# Stepper_Motor_Driver_2.net
KiCad netlist of a schematic drawn in Altium Designer
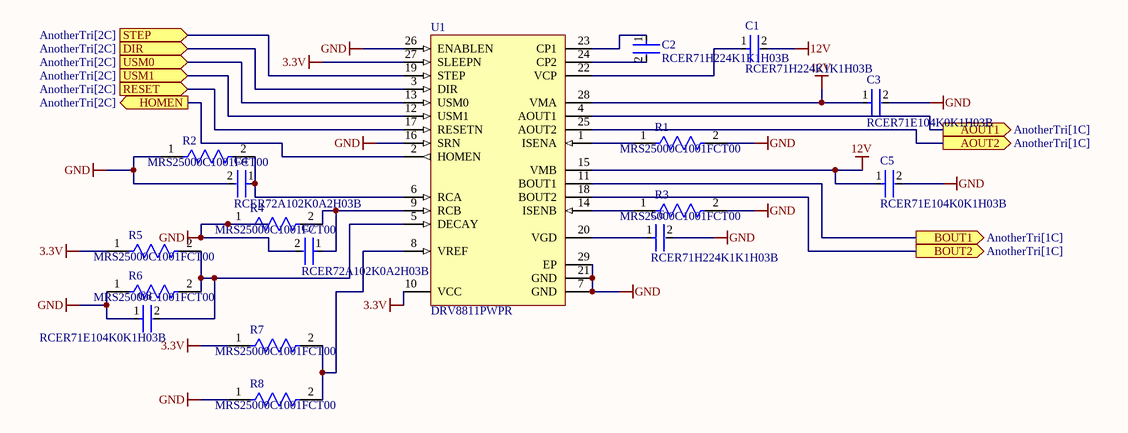
[diagram p0: Stepper Motor Driver 2.SchDoc]

(export (version "E")
  (design (tool "Eeschema 10.0.6"))
  (components
    (comp (ref "C1")
      (value "RCER71H224K1K1H03B")
      (footprint "FP-RCE1K1-2_5-MFG")
      (description "Cap Ceramic Monolithic 220nF 50V 10% Thru-Hole Bulk")
      (fields (field (name "TOLERANCE") "10%"))
      (libsource (lib "Altium Content Vault") (part "02cd4be3c70576c341d710602a673aa"))
    )
    (comp (ref "C2")
      (value "RCER71H224K1K1H03B")
      (footprint "FP-RCE1K1-2_5-MFG")
      (description "Cap Ceramic Monolithic 220nF 50V 10% Thru-Hole Bulk")
      (fields (field (name "TOLERANCE") "10%"))
      (libsource (lib "Altium Content Vault") (part "02cd4be3c70576c341d710602a673aa"))
    )
    (comp (ref "C3")
      (value "RCER71E104K0K1H03B")
      (footprint "FP-RCE0K1-MFG")
      (description "Cap Ceramic 100nF 25V X7R ±10% Radial 5mm +125°C Automotive Bulk")
      (libsource (lib "Altium Content Vault") (part "b4654b650e69147ec39a6b967a45e02"))
    )
    (comp (ref "C4")
      (value "RCER72A102K0A2H03B")
      (footprint "FP-RCE0DB-MFG")
      (description "Cap Ceramic 1nF 100V X7R ±10% Radial 2.5mm +125°C Bulk")
      (fields (field (name "TOLERANCE") "10%"))
      (libsource (lib "Altium Content Vault") (part "b4654b650e69147ec39a6b967a45e02"))
    )
    (comp (ref "C5")
      (value "RCER71E104K0K1H03B")
      (footprint "FP-RCE0K1-MFG")
      (description "Cap Ceramic 100nF 25V X7R ±10% Radial 5mm +125°C Automotive Bulk")
      (libsource (lib "Altium Content Vault") (part "b4654b650e69147ec39a6b967a45e02"))
    )
    (comp (ref "C6")
      (value "RCER71H224K1K1H03B")
      (footprint "FP-RCE1K1-2_5-MFG")
      (description "Cap Ceramic Monolithic 220nF 50V 10% Thru-Hole Bulk")
      (fields (field (name "TOLERANCE") "10%"))
      (libsource (lib "Altium Content Vault") (part "02cd4be3c70576c341d710602a673aa"))
    )
    (comp (ref "C7")
      (value "RCER72A102K0A2H03B")
      (footprint "FP-RCE0DB-MFG")
      (description "Cap Ceramic 1nF 100V X7R ±10% Radial 2.5mm +125°C Bulk")
      (fields (field (name "TOLERANCE") "10%"))
      (libsource (lib "Altium Content Vault") (part "b4654b650e69147ec39a6b967a45e02"))
    )
    (comp (ref "C8")
      (value "RCER71E104K0K1H03B")
      (footprint "FP-RCE0K1-MFG")
      (description "Cap Ceramic 100nF 25V X7R ±10% Radial 5mm +125°C Automotive Bulk")
      (libsource (lib "Altium Content Vault") (part "b4654b650e69147ec39a6b967a45e02"))
    )
    (comp (ref "R1")
      (value "MRS25000C1001FCT00")
      (footprint "FP-MRS25-MFG")
      (description "RES 1K OHM 0.6W 1% AXIAL")
      (fields (field (name "TOLERANCE") "1%"))
      (libsource (lib "Altium Content Vault") (part "1029c3af85768c4190bb7ad29bc67b5"))
    )
    (comp (ref "R2")
      (value "MRS25000C1001FCT00")
      (footprint "FP-MRS25-MFG")
      (description "RES 1K OHM 0.6W 1% AXIAL")
      (fields (field (name "TOLERANCE") "1%"))
      (libsource (lib "Altium Content Vault") (part "1029c3af85768c4190bb7ad29bc67b5"))
    )
    (comp (ref "R3")
      (value "MRS25000C1001FCT00")
      (footprint "FP-MRS25-MFG")
      (description "RES 1K OHM 0.6W 1% AXIAL")
      (fields (field (name "TOLERANCE") "1%"))
      (libsource (lib "Altium Content Vault") (part "1029c3af85768c4190bb7ad29bc67b5"))
    )
    (comp (ref "R4")
      (value "MRS25000C1001FCT00")
      (footprint "FP-MRS25-MFG")
      (description "RES 1K OHM 0.6W 1% AXIAL")
      (fields (field (name "TOLERANCE") "1%"))
      (libsource (lib "Altium Content Vault") (part "1029c3af85768c4190bb7ad29bc67b5"))
    )
    (comp (ref "R5")
      (value "MRS25000C1001FCT00")
      (footprint "FP-MRS25-MFG")
      (description "RES 1K OHM 0.6W 1% AXIAL")
      (fields (field (name "TOLERANCE") "1%"))
      (libsource (lib "Altium Content Vault") (part "1029c3af85768c4190bb7ad29bc67b5"))
    )
    (comp (ref "R6")
      (value "MRS25000C1001FCT00")
      (footprint "FP-MRS25-MFG")
      (description "RES 1K OHM 0.6W 1% AXIAL")
      (fields (field (name "TOLERANCE") "1%"))
      (libsource (lib "Altium Content Vault") (part "1029c3af85768c4190bb7ad29bc67b5"))
    )
    (comp (ref "R7")
      (value "MRS25000C1001FCT00")
      (footprint "FP-MRS25-MFG")
      (description "RES 1K OHM 0.6W 1% AXIAL")
      (fields (field (name "TOLERANCE") "1%"))
      (libsource (lib "Altium Content Vault") (part "1029c3af85768c4190bb7ad29bc67b5"))
    )
    (comp (ref "R8")
      (value "MRS25000C1001FCT00")
      (footprint "FP-MRS25-MFG")
      (description "RES 1K OHM 0.6W 1% AXIAL")
      (fields (field (name "TOLERANCE") "1%"))
      (libsource (lib "Altium Content Vault") (part "1029c3af85768c4190bb7ad29bc67b5"))
    )
    (comp (ref "U1")
      (value "DRV8811PWPR")
      (footprint "PWP0028C_L")
      (libsource (lib "Altium Content Vault") (part "TI-DRV8811PWP28-5230X2750TP"))
    )
  )
  (nets
    (net (code "1") (name "/AOUT1") (class "Default")
      (node (ref "U1") (pin "4") (pinfunction "AOUT1_4") (pintype "power_in"))
    )
    (net (code "2") (name "/AOUT2") (class "Default")
      (node (ref "U1") (pin "25") (pinfunction "AOUT2_25") (pintype "power_in"))
    )
    (net (code "3") (name "/BOUT1") (class "Default")
      (node (ref "U1") (pin "11") (pinfunction "BOUT1_11") (pintype "power_in"))
    )
    (net (code "4") (name "/BOUT2") (class "Default")
      (node (ref "U1") (pin "18") (pinfunction "BOUT2_18") (pintype "power_in"))
    )
    (net (code "5") (name "/DIR") (class "Default")
      (node (ref "U1") (pin "3") (pinfunction "DIR_3") (pintype "input"))
    )
    (net (code "6") (name "/HOMEN") (class "Default")
      (node (ref "U1") (pin "2") (pinfunction "HOMEN_2") (pintype "output"))
    )
    (net (code "7") (name "/RESET") (class "Default")
      (node (ref "U1") (pin "17") (pinfunction "RESETN_17") (pintype "input"))
    )
    (net (code "8") (name "/STEP") (class "Default")
      (node (ref "U1") (pin "19") (pinfunction "STEP_19") (pintype "input"))
    )
    (net (code "9") (name "/USM0") (class "Default")
      (node (ref "U1") (pin "13") (pinfunction "USM0_13") (pintype "input"))
    )
    (net (code "10") (name "/USM1") (class "Default")
      (node (ref "U1") (pin "12") (pinfunction "USM1_12") (pintype "input"))
    )
    (net (code "11") (name "3.3V") (class "Default")
      (node (ref "R5") (pin "1") (pinfunction "1_1") (pintype "passive"))
      (node (ref "R7") (pin "1") (pinfunction "1_1") (pintype "passive"))
      (node (ref "U1") (pin "10") (pinfunction "VCC_10") (pintype "power_in"))
      (node (ref "U1") (pin "27") (pinfunction "SLEEPN_27") (pintype "input"))
    )
    (net (code "12") (name "12V") (class "Default")
      (node (ref "C1") (pin "2") (pinfunction "2_2") (pintype "passive"))
      (node (ref "C3") (pin "1") (pinfunction "1_1") (pintype "passive"))
      (node (ref "C5") (pin "1") (pinfunction "1_1") (pintype "passive"))
      (node (ref "U1") (pin "15") (pinfunction "VMB_15") (pintype "power_in"))
      (node (ref "U1") (pin "28") (pinfunction "VMA_28") (pintype "power_in"))
    )
    (net (code "13") (name "GND") (class "Default")
      (node (ref "C3") (pin "2") (pinfunction "2_2") (pintype "passive"))
      (node (ref "C4") (pin "2") (pinfunction "2_2") (pintype "passive"))
      (node (ref "C5") (pin "2") (pinfunction "2_2") (pintype "passive"))
      (node (ref "C6") (pin "2") (pinfunction "2_2") (pintype "passive"))
      (node (ref "C7") (pin "2") (pinfunction "2_2") (pintype "passive"))
      (node (ref "C8") (pin "1") (pinfunction "1_1") (pintype "passive"))
      (node (ref "R1") (pin "2") (pinfunction "2_2") (pintype "passive"))
      (node (ref "R2") (pin "1") (pinfunction "1_1") (pintype "passive"))
      (node (ref "R3") (pin "2") (pinfunction "2_2") (pintype "passive"))
      (node (ref "R4") (pin "1") (pinfunction "1_1") (pintype "passive"))
      (node (ref "R6") (pin "1") (pinfunction "1_1") (pintype "passive"))
      (node (ref "R8") (pin "1") (pinfunction "1_1") (pintype "passive"))
      (node (ref "U1") (pin "16") (pinfunction "SRN_16") (pintype "input"))
      (node (ref "U1") (pin "21") (pinfunction "GND_21") (pintype "power_in"))
      (node (ref "U1") (pin "26") (pinfunction "ENABLEN_26") (pintype "input"))
      (node (ref "U1") (pin "29") (pinfunction "EP_29") (pintype "power_in"))
      (node (ref "U1") (pin "7") (pinfunction "GND_7") (pintype "power_in"))
    )
    (net (code "14") (name "Net-(U1-CP1)") (class "Default")
      (node (ref "C2") (pin "1") (pinfunction "1_1") (pintype "passive"))
      (node (ref "U1") (pin "23") (pinfunction "CP1_23") (pintype "passive"))
    )
    (net (code "15") (name "Net-(U1-CP2)") (class "Default")
      (node (ref "C2") (pin "2") (pinfunction "2_2") (pintype "passive"))
      (node (ref "U1") (pin "24") (pinfunction "CP2_24") (pintype "passive"))
    )
    (net (code "16") (name "Net-(U1-DECAY)") (class "Default")
      (node (ref "C8") (pin "2") (pinfunction "2_2") (pintype "passive"))
      (node (ref "R5") (pin "2") (pinfunction "2_2") (pintype "passive"))
      (node (ref "R6") (pin "2") (pinfunction "2_2") (pintype "passive"))
      (node (ref "U1") (pin "5") (pinfunction "DECAY_5") (pintype "input"))
    )
    (net (code "17") (name "Net-(U1-ISENA)") (class "Default")
      (node (ref "R1") (pin "1") (pinfunction "1_1") (pintype "passive"))
      (node (ref "U1") (pin "1") (pinfunction "ISENA_1") (pintype "input"))
    )
    (net (code "18") (name "Net-(U1-ISENB)") (class "Default")
      (node (ref "R3") (pin "1") (pinfunction "1_1") (pintype "passive"))
      (node (ref "U1") (pin "14") (pinfunction "ISENB_14") (pintype "input"))
    )
    (net (code "19") (name "Net-(U1-RCA)") (class "Default")
      (node (ref "C4") (pin "1") (pinfunction "1_1") (pintype "passive"))
      (node (ref "R2") (pin "2") (pinfunction "2_2") (pintype "passive"))
      (node (ref "U1") (pin "6") (pinfunction "RCA_6") (pintype "input"))
    )
    (net (code "20") (name "Net-(U1-RCB)") (class "Default")
      (node (ref "C7") (pin "1") (pinfunction "1_1") (pintype "passive"))
      (node (ref "R4") (pin "2") (pinfunction "2_2") (pintype "passive"))
      (node (ref "U1") (pin "9") (pinfunction "RCB_9") (pintype "input"))
    )
    (net (code "21") (name "Net-(U1-VCP)") (class "Default")
      (node (ref "C1") (pin "1") (pinfunction "1_1") (pintype "passive"))
      (node (ref "U1") (pin "22") (pinfunction "VCP_22") (pintype "power_in"))
    )
    (net (code "22") (name "Net-(U1-VGD)") (class "Default")
      (node (ref "C6") (pin "1") (pinfunction "1_1") (pintype "passive"))
      (node (ref "U1") (pin "20") (pinfunction "VGD_20") (pintype "power_in"))
    )
    (net (code "23") (name "Net-(U1-VREF)") (class "Default")
      (node (ref "R7") (pin "2") (pinfunction "2_2") (pintype "passive"))
      (node (ref "R8") (pin "2") (pinfunction "2_2") (pintype "passive"))
      (node (ref "U1") (pin "8") (pinfunction "VREF_8") (pintype "input"))
    )
  )
)
